# Gamebuino.net
KiCad netlist of a schematic drawn in Altium Designer
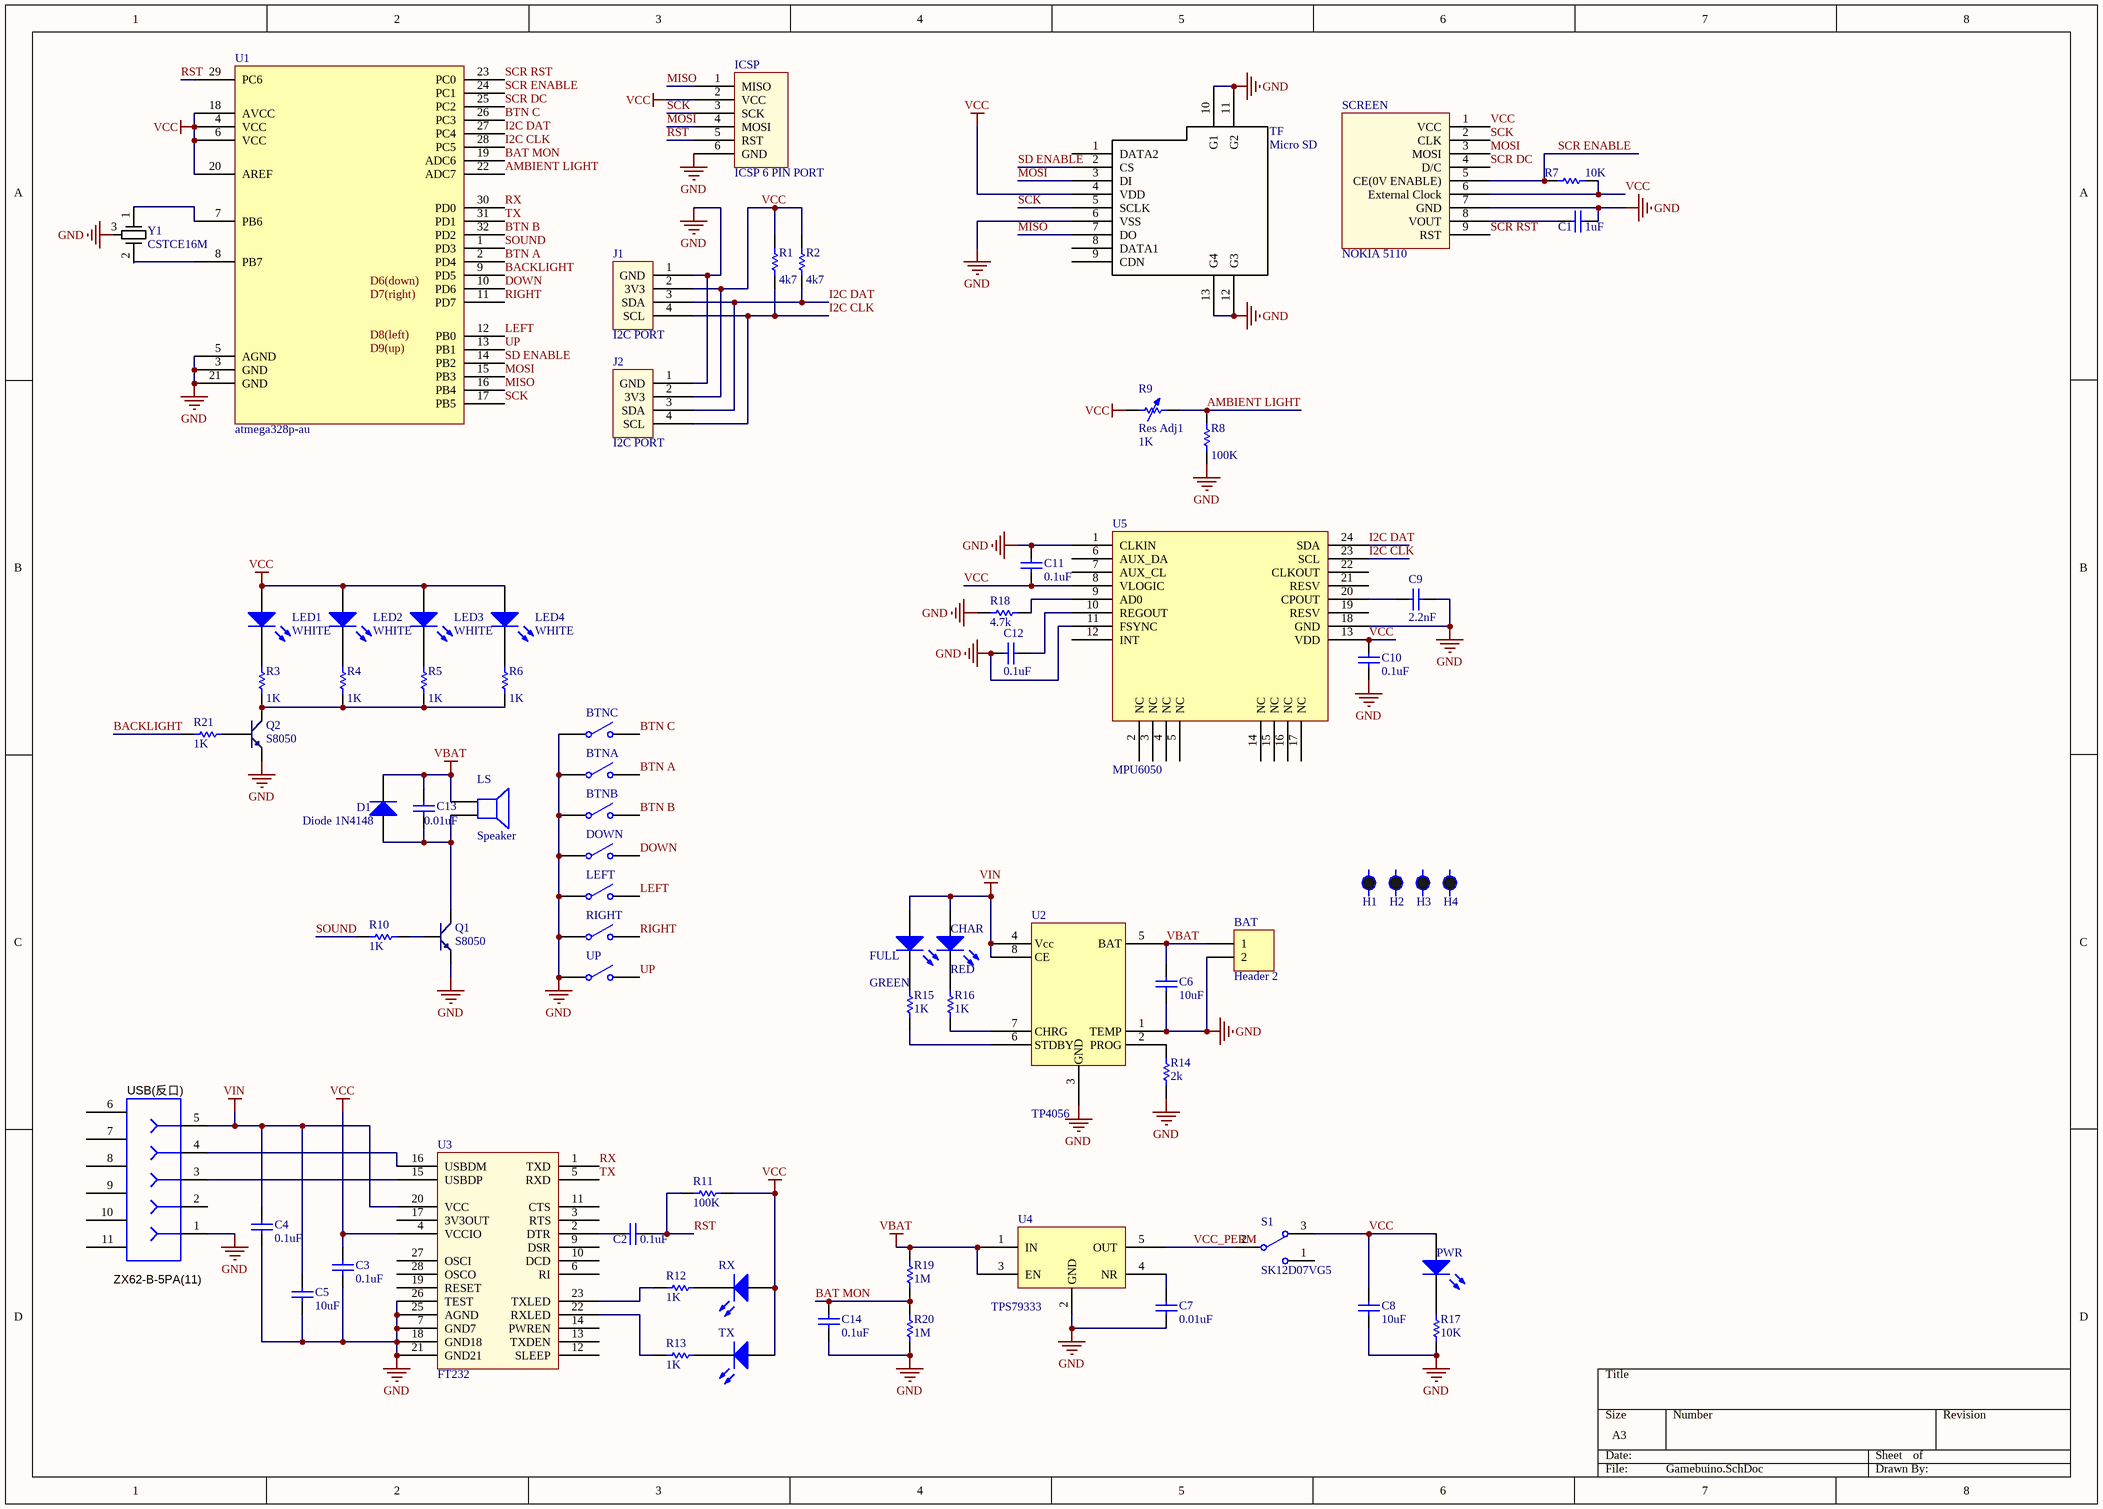
[diagram p0: Gamebuino.SchDoc]

(export (version "E")
  (design (tool "Eeschema 10.0.6"))
  (components
    (comp (ref "BAT")
      (value "Header 2")
      (footprint "BAT")
      (description "Header, 2-Pin")
      (fields (field (name "PUBLISHER") "Altium Limited"))
      (libsource (lib "Miscellaneous Connectors") (part "Header 2"))
    )
    (comp (ref "BTNA")
      (value "SW-SPST")
      (footprint "KEY5")
      (description "Single-Pole, Single-Throw Switch")
      (fields (field (name "PUBLISHER") "Altium Limited"))
      (libsource (lib "Miscellaneous Devices") (part "SW-SPST"))
    )
    (comp (ref "BTNB")
      (value "SW-SPST")
      (footprint "KEY5")
      (description "Single-Pole, Single-Throw Switch")
      (fields (field (name "PUBLISHER") "Altium Limited"))
      (libsource (lib "Miscellaneous Devices") (part "SW-SPST"))
    )
    (comp (ref "BTNC")
      (value "SW-SPST")
      (footprint "KEY5")
      (description "Single-Pole, Single-Throw Switch")
      (fields (field (name "PUBLISHER") "Altium Limited"))
      (libsource (lib "Miscellaneous Devices") (part "SW-SPST"))
    )
    (comp (ref "C1")
      (value "1uF")
      (footprint "6-0805_N")
      (description "Capacitor")
      (fields (field (name "Comment") "Cap") (field (name "PUBLISHER") "Altium Limited"))
      (libsource (lib "Miscellaneous Devices") (part "Cap"))
    )
    (comp (ref "C2")
      (value "0.1uF")
      (footprint "6-0805_N")
      (description "Capacitor")
      (fields (field (name "Comment") "Cap") (field (name "PUBLISHER") "Altium Limited"))
      (libsource (lib "Miscellaneous Devices") (part "Cap"))
    )
    (comp (ref "C3")
      (value "0.1uF")
      (footprint "6-0805_N")
      (description "Capacitor")
      (fields (field (name "Comment") "Cap") (field (name "PUBLISHER") "Altium Limited"))
      (libsource (lib "Miscellaneous Devices") (part "Cap"))
    )
    (comp (ref "C4")
      (value "0.1uF")
      (footprint "6-0805_N")
      (description "Capacitor")
      (fields (field (name "Comment") "Cap") (field (name "PUBLISHER") "Altium Limited"))
      (libsource (lib "Miscellaneous Devices") (part "Cap"))
    )
    (comp (ref "C5")
      (value "10uF")
      (footprint "6-0805_N")
      (description "Capacitor")
      (fields (field (name "Comment") "Cap") (field (name "PUBLISHER") "Altium Limited"))
      (libsource (lib "Miscellaneous Devices") (part "Cap"))
    )
    (comp (ref "C6")
      (value "10uF")
      (footprint "6-0805_N")
      (description "Capacitor")
      (fields (field (name "Comment") "Cap") (field (name "PUBLISHER") "Altium Limited"))
      (libsource (lib "Miscellaneous Devices") (part "Cap"))
    )
    (comp (ref "C7")
      (value "0.01uF")
      (footprint "6-0805_N")
      (description "Capacitor")
      (fields (field (name "Comment") "Cap") (field (name "PUBLISHER") "Altium Limited"))
      (libsource (lib "Miscellaneous Devices") (part "Cap"))
    )
    (comp (ref "C8")
      (value "10uF")
      (footprint "6-0805_N")
      (description "Capacitor")
      (fields (field (name "Comment") "Cap") (field (name "PUBLISHER") "Altium Limited"))
      (libsource (lib "Miscellaneous Devices") (part "Cap"))
    )
    (comp (ref "C9")
      (value "2.2nF")
      (footprint "6-0805_N")
      (description "Capacitor")
      (fields (field (name "Comment") "Cap") (field (name "PUBLISHER") "Altium Limited"))
      (libsource (lib "Miscellaneous Devices") (part "Cap"))
    )
    (comp (ref "C10")
      (value "0.1uF")
      (footprint "6-0805_N")
      (description "Capacitor")
      (fields (field (name "Comment") "Cap") (field (name "PUBLISHER") "Altium Limited"))
      (libsource (lib "Miscellaneous Devices") (part "Cap"))
    )
    (comp (ref "C11")
      (value "0.1uF")
      (footprint "6-0805_N")
      (description "Capacitor")
      (fields (field (name "Comment") "Cap") (field (name "PUBLISHER") "Altium Limited"))
      (libsource (lib "Miscellaneous Devices") (part "Cap"))
    )
    (comp (ref "C12")
      (value "0.1uF")
      (footprint "6-0805_N")
      (description "Capacitor")
      (fields (field (name "Comment") "Cap") (field (name "PUBLISHER") "Altium Limited"))
      (libsource (lib "Miscellaneous Devices") (part "Cap"))
    )
    (comp (ref "C13")
      (value "0.01uF")
      (footprint "6-0805_N")
      (description "Capacitor")
      (fields (field (name "Comment") "Cap") (field (name "PUBLISHER") "Altium Limited"))
      (libsource (lib "Miscellaneous Devices") (part "Cap"))
    )
    (comp (ref "C14")
      (value "0.1uF")
      (footprint "6-0805_N")
      (description "Capacitor")
      (fields (field (name "Comment") "Cap") (field (name "PUBLISHER") "Altium Limited"))
      (libsource (lib "Miscellaneous Devices") (part "Cap"))
    )
    (comp (ref "CHAR")
      (value "RED")
      (footprint "6-0805_N")
      (description "Typical INFRARED GaAs LED")
      (fields (field (name "PUBLISHER") "Altium Limited"))
      (libsource (lib "Miscellaneous Devices") (part "LED0"))
    )
    (comp (ref "D1")
      (value "Diode 1N4148")
      (footprint "12Z-2010")
      (description "High Conductance Fast Diode")
      (fields (field (name "PUBLISHER") "Altium Limited"))
      (libsource (lib "Miscellaneous Devices") (part "Diode 1N4148"))
    )
    (comp (ref "DOWN")
      (value "SW-SPST")
      (footprint "KEY5")
      (description "Single-Pole, Single-Throw Switch")
      (fields (field (name "PUBLISHER") "Altium Limited"))
      (libsource (lib "Miscellaneous Devices") (part "SW-SPST"))
    )
    (comp (ref "FULL")
      (value "GREEN")
      (footprint "6-0805_N")
      (description "Typical INFRARED GaAs LED")
      (fields (field (name "PUBLISHER") "Altium Limited"))
      (libsource (lib "Miscellaneous Devices") (part "LED0"))
    )
    (comp (ref "H1") (value "HOLE") (footprint "HOLE_3.0") (libsource (lib "mp3_digital") (part "HOLE")))
    (comp (ref "H2") (value "HOLE") (footprint "HOLE_3.0") (libsource (lib "mp3_digital") (part "HOLE")))
    (comp (ref "H3") (value "HOLE") (footprint "HOLE_3.0") (libsource (lib "mp3_digital") (part "HOLE")))
    (comp (ref "H4") (value "HOLE") (footprint "HOLE_3.0") (libsource (lib "mp3_digital") (part "HOLE")))
    (comp (ref "ICSP")
      (value "ICSP 6 PIN PORT")
      (footprint "CONN6-1mm")
      (libsource (lib "Gamebuino") (part "ICSP"))
    )
    (comp (ref "J1")
      (value "I2C PORT")
      (footprint "CONN4_/wTestPoint")
      (libsource (lib "Gamebuino") (part "Component_1"))
    )
    (comp (ref "J2")
      (value "I2C PORT")
      (footprint "CONN4_/wTestPoint")
      (libsource (lib "Gamebuino") (part "Component_1"))
    )
    (comp (ref "LED1")
      (value "WHITE")
      (footprint "6-0805_N")
      (description "Typical INFRARED GaAs LED")
      (fields (field (name "PUBLISHER") "Altium Limited"))
      (libsource (lib "Miscellaneous Devices") (part "LED0"))
    )
    (comp (ref "LED2")
      (value "WHITE")
      (footprint "6-0805_N")
      (description "Typical INFRARED GaAs LED")
      (fields (field (name "PUBLISHER") "Altium Limited"))
      (libsource (lib "Miscellaneous Devices") (part "LED0"))
    )
    (comp (ref "LED3")
      (value "WHITE")
      (footprint "6-0805_N")
      (description "Typical INFRARED GaAs LED")
      (fields (field (name "PUBLISHER") "Altium Limited"))
      (libsource (lib "Miscellaneous Devices") (part "LED0"))
    )
    (comp (ref "LED4")
      (value "WHITE")
      (footprint "6-0805_N")
      (description "Typical INFRARED GaAs LED")
      (fields (field (name "PUBLISHER") "Altium Limited"))
      (libsource (lib "Miscellaneous Devices") (part "LED0"))
    )
    (comp (ref "LEFT")
      (value "SW-SPST")
      (footprint "KEY5")
      (description "Single-Pole, Single-Throw Switch")
      (fields (field (name "PUBLISHER") "Altium Limited"))
      (libsource (lib "Miscellaneous Devices") (part "SW-SPST"))
    )
    (comp (ref "LS")
      (value "Speaker")
      (footprint "Speaker")
      (description "Loudspeaker")
      (fields (field (name "PUBLISHER") "Altium Limited"))
      (libsource (lib "Miscellaneous Devices") (part "Speaker"))
    )
    (comp (ref "PWR")
      (value "LED0")
      (footprint "6-0805_N")
      (description "Typical INFRARED GaAs LED")
      (fields (field (name "PUBLISHER") "Altium Limited"))
      (libsource (lib "Miscellaneous Devices") (part "LED0"))
    )
    (comp (ref "Q1")
      (value "S8050")
      (footprint "SOT-23R")
      (description "8050/BCW846/BCW847")
      (libsource (lib "mp3_analog") (part "NPN"))
    )
    (comp (ref "Q2")
      (value "S8050")
      (footprint "SOT-23R")
      (description "8050/BCW846/BCW847")
      (libsource (lib "mp3_analog") (part "NPN"))
    )
    (comp (ref "R1")
      (value "4k7")
      (footprint "6-0805_N")
      (description "Resistor")
      (fields (field (name "Comment") "Res1") (field (name "PUBLISHER") "Altium Limited"))
      (libsource (lib "Miscellaneous Devices") (part "Res1"))
    )
    (comp (ref "R2")
      (value "4k7")
      (footprint "6-0805_N")
      (description "Resistor")
      (fields (field (name "Comment") "Res1") (field (name "PUBLISHER") "Altium Limited"))
      (libsource (lib "Miscellaneous Devices") (part "Res1"))
    )
    (comp (ref "R3")
      (value "1K")
      (footprint "6-0805_N")
      (description "Resistor")
      (fields (field (name "Comment") "Res1") (field (name "PUBLISHER") "Altium Limited"))
      (libsource (lib "Miscellaneous Devices") (part "Res1"))
    )
    (comp (ref "R4")
      (value "1K")
      (footprint "6-0805_N")
      (description "Resistor")
      (fields (field (name "Comment") "Res1") (field (name "PUBLISHER") "Altium Limited"))
      (libsource (lib "Miscellaneous Devices") (part "Res1"))
    )
    (comp (ref "R5")
      (value "1K")
      (footprint "6-0805_N")
      (description "Resistor")
      (fields (field (name "Comment") "Res1") (field (name "PUBLISHER") "Altium Limited"))
      (libsource (lib "Miscellaneous Devices") (part "Res1"))
    )
    (comp (ref "R6")
      (value "1K")
      (footprint "6-0805_N")
      (description "Resistor")
      (fields (field (name "Comment") "Res1") (field (name "PUBLISHER") "Altium Limited"))
      (libsource (lib "Miscellaneous Devices") (part "Res1"))
    )
    (comp (ref "R7")
      (value "10K")
      (footprint "6-0805_N")
      (description "Resistor")
      (fields (field (name "Comment") "Res1") (field (name "PUBLISHER") "Altium Limited"))
      (libsource (lib "Miscellaneous Devices") (part "Res1"))
    )
    (comp (ref "R8")
      (value "100K")
      (footprint "6-0805_N")
      (description "Resistor")
      (fields (field (name "Comment") "Res1") (field (name "PUBLISHER") "Altium Limited"))
      (libsource (lib "Miscellaneous Devices") (part "Res1"))
    )
    (comp (ref "R9")
      (value "Res Adj1")
      (footprint "light_sensor")
      (description "Variable Resistor")
      (fields (field (name "ALTIUM_VALUE") "1K") (field (name "PUBLISHER") "Altium Limited"))
      (libsource (lib "Miscellaneous Devices") (part "Res Adj1"))
    )
    (comp (ref "R10")
      (value "1K")
      (footprint "6-0805_N")
      (description "Resistor")
      (fields (field (name "Comment") "Res1") (field (name "PUBLISHER") "Altium Limited"))
      (libsource (lib "Miscellaneous Devices") (part "Res1"))
    )
    (comp (ref "R11")
      (value "100K")
      (footprint "6-0805_N")
      (description "Resistor")
      (fields (field (name "Comment") "Res1") (field (name "PUBLISHER") "Altium Limited"))
      (libsource (lib "Miscellaneous Devices") (part "Res1"))
    )
    (comp (ref "R12")
      (value "1K")
      (footprint "6-0805_N")
      (description "Resistor")
      (fields (field (name "Comment") "Res1") (field (name "PUBLISHER") "Altium Limited"))
      (libsource (lib "Miscellaneous Devices") (part "Res1"))
    )
    (comp (ref "R13")
      (value "1K")
      (footprint "6-0805_N")
      (description "Resistor")
      (fields (field (name "Comment") "Res1") (field (name "PUBLISHER") "Altium Limited"))
      (libsource (lib "Miscellaneous Devices") (part "Res1"))
    )
    (comp (ref "R14")
      (value "2k")
      (footprint "6-0805_N")
      (description "Resistor")
      (fields (field (name "Comment") "Res1") (field (name "PUBLISHER") "Altium Limited"))
      (libsource (lib "Miscellaneous Devices") (part "Res1"))
    )
    (comp (ref "R15")
      (value "1K")
      (footprint "6-0805_N")
      (description "Resistor")
      (fields (field (name "Comment") "Res1") (field (name "PUBLISHER") "Altium Limited"))
      (libsource (lib "Miscellaneous Devices") (part "Res1"))
    )
    (comp (ref "R16")
      (value "1K")
      (footprint "6-0805_N")
      (description "Resistor")
      (fields (field (name "Comment") "Res1") (field (name "PUBLISHER") "Altium Limited"))
      (libsource (lib "Miscellaneous Devices") (part "Res1"))
    )
    (comp (ref "R17")
      (value "10K")
      (footprint "6-0805_N")
      (description "Resistor")
      (fields (field (name "Comment") "Res1") (field (name "PUBLISHER") "Altium Limited"))
      (libsource (lib "Miscellaneous Devices") (part "Res1"))
    )
    (comp (ref "R18")
      (value "4.7k")
      (footprint "6-0805_N")
      (description "Resistor")
      (fields (field (name "Comment") "Res1") (field (name "PUBLISHER") "Altium Limited"))
      (libsource (lib "Miscellaneous Devices") (part "Res1"))
    )
    (comp (ref "R19")
      (value "1M")
      (footprint "6-0805_N")
      (description "Resistor")
      (fields (field (name "Comment") "Res1") (field (name "PUBLISHER") "Altium Limited"))
      (libsource (lib "Miscellaneous Devices") (part "Res1"))
    )
    (comp (ref "R20")
      (value "1M")
      (footprint "6-0805_N")
      (description "Resistor")
      (fields (field (name "Comment") "Res1") (field (name "PUBLISHER") "Altium Limited"))
      (libsource (lib "Miscellaneous Devices") (part "Res1"))
    )
    (comp (ref "R21")
      (value "1K")
      (footprint "6-0805_N")
      (description "Resistor")
      (fields (field (name "Comment") "Res1") (field (name "PUBLISHER") "Altium Limited"))
      (libsource (lib "Miscellaneous Devices") (part "Res1"))
    )
    (comp (ref "RIGHT")
      (value "SW-SPST")
      (footprint "KEY5")
      (description "Single-Pole, Single-Throw Switch")
      (fields (field (name "PUBLISHER") "Altium Limited"))
      (libsource (lib "Miscellaneous Devices") (part "SW-SPST"))
    )
    (comp (ref "RX")
      (value "LED0")
      (footprint "6-0805_N")
      (description "Typical INFRARED GaAs LED")
      (fields (field (name "PUBLISHER") "Altium Limited"))
      (libsource (lib "Miscellaneous Devices") (part "LED0"))
    )
    (comp (ref "S1")
      (value "SK12D07VG5")
      (footprint "DIP10")
      (description "SPDT Subminiature Toggle Switch, Right Angle Mounting, Vertical Actuation")
      (fields (field (name "PUBLISHER") "Altium Limited"))
      (libsource (lib "Miscellaneous Devices") (part "SW-SPDT"))
    )
    (comp (ref "SCREEN")
      (value "NOKIA 5110")
      (footprint "5110_bare")
      (libsource (lib "Gamebuino") (part "NOKIA 5110"))
    )
    (comp (ref "TF") (value "Micro SD") (footprint "tf") (libsource (lib "MP3 NANO") (part "Micro SD")))
    (comp (ref "TX")
      (value "LED0")
      (footprint "6-0805_N")
      (description "Typical INFRARED GaAs LED")
      (fields (field (name "PUBLISHER") "Altium Limited"))
      (libsource (lib "Miscellaneous Devices") (part "LED0"))
    )
    (comp (ref "U1")
      (value "atmega328p-au")
      (footprint "TQFP-32N-1")
      (libsource (lib "dakaqi") (part "atmega328p-au"))
    )
    (comp (ref "U2") (value "TP4056") (footprint "SOP-PP-8") (libsource (lib "mp3_digital") (part "TP4056")))
    (comp (ref "U3")
      (value "FT232")
      (footprint "LC-SSOP-28_208mil")
      (libsource (lib "Gamebuino") (part "FT232"))
    )
    (comp (ref "U4")
      (value "TPS79333")
      (footprint "SOT-23-5")
      (libsource (lib "mp3_analog") (part "TPS79333"))
    )
    (comp (ref "U5") (value "MPU6050") (footprint "QFN-24A") (libsource (lib "microsizhou") (part "MPU6050")))
    (comp (ref "UP")
      (value "SW-SPST")
      (footprint "KEY5")
      (description "Single-Pole, Single-Throw Switch")
      (fields (field (name "PUBLISHER") "Altium Limited"))
      (libsource (lib "Miscellaneous Devices") (part "SW-SPST"))
    )
    (comp (ref "USB(反口)")
      (value "ZX62-B-5PA(11)")
      (footprint "CONN_USB_micro_ZX62-B-5PA")
      (description "Connector, micro USB Type B, Receptacle, R/A, SMD")
      (fields
        (field (name "MANUFACTURER") "Hirose Electric Co. Ltd.")
        (field (name "SYMBOLCREATOR") "a0411947")
        (field (name "PUBLISHER") "Texas Instruments")
      )
      (libsource (lib "Focus1Beta1STM32") (part "ZX62M-B-5P"))
    )
    (comp (ref "Y1") (value "CSTCE16M") (footprint "cstce8m") (libsource (lib "dakaqi") (part "cstce8m")))
  )
  (nets
    (net (code "1") (name "/AMBIENT LIGHT") (class "Default")
      (node (ref "R8") (pin "2") (pinfunction "2_2") (pintype "passive"))
      (node (ref "R9") (pin "2") (pinfunction "2_2") (pintype "passive"))
      (node (ref "U1") (pin "22") (pinfunction "ADC7_22") (pintype "passive"))
    )
    (net (code "2") (name "/BACKLIGHT") (class "Default")
      (node (ref "R21") (pin "1") (pinfunction "1_1") (pintype "passive"))
      (node (ref "U1") (pin "9") (pinfunction "PD5_9") (pintype "passive"))
    )
    (net (code "3") (name "/BAT MON") (class "Default")
      (node (ref "C14") (pin "1") (pinfunction "1_1") (pintype "passive"))
      (node (ref "R19") (pin "1") (pinfunction "1_1") (pintype "passive"))
      (node (ref "R20") (pin "2") (pinfunction "2_2") (pintype "passive"))
      (node (ref "U1") (pin "19") (pinfunction "ADC6_19") (pintype "passive"))
    )
    (net (code "4") (name "/BTN A") (class "Default")
      (node (ref "BTNA") (pin "2") (pinfunction "NO_2") (pintype "passive"))
      (node (ref "U1") (pin "2") (pinfunction "PD4_2") (pintype "passive"))
    )
    (net (code "5") (name "/BTN B") (class "Default")
      (node (ref "BTNB") (pin "2") (pinfunction "NO_2") (pintype "passive"))
      (node (ref "U1") (pin "32") (pinfunction "PD2_32") (pintype "passive"))
    )
    (net (code "6") (name "/BTN C") (class "Default")
      (node (ref "BTNC") (pin "2") (pinfunction "NO_2") (pintype "passive"))
      (node (ref "U1") (pin "26") (pinfunction "PC3_26") (pintype "passive"))
    )
    (net (code "11") (name "/DOWN") (class "Default")
      (node (ref "DOWN") (pin "2") (pinfunction "NO_2") (pintype "passive"))
      (node (ref "U1") (pin "10") (pinfunction "PD6_10") (pintype "passive"))
    )
    (net (code "12") (name "/I2C CLK") (class "Default")
      (node (ref "J1") (pin "4") (pinfunction "SCL_4") (pintype "passive"))
      (node (ref "J2") (pin "4") (pinfunction "SCL_4") (pintype "passive"))
      (node (ref "R1") (pin "1") (pinfunction "1_1") (pintype "passive"))
      (node (ref "U1") (pin "28") (pinfunction "PC5_28") (pintype "passive"))
      (node (ref "U5") (pin "23") (pinfunction "SCL_23") (pintype "passive"))
    )
    (net (code "13") (name "/I2C DAT") (class "Default")
      (node (ref "J1") (pin "3") (pinfunction "SDA_3") (pintype "passive"))
      (node (ref "J2") (pin "3") (pinfunction "SDA_3") (pintype "passive"))
      (node (ref "R2") (pin "1") (pinfunction "1_1") (pintype "passive"))
      (node (ref "U1") (pin "27") (pinfunction "PC4_27") (pintype "passive"))
      (node (ref "U5") (pin "24") (pinfunction "SDA_24") (pintype "passive"))
    )
    (net (code "14") (name "/LEFT") (class "Default")
      (node (ref "LEFT") (pin "2") (pinfunction "NO_2") (pintype "passive"))
      (node (ref "U1") (pin "12") (pinfunction "PB0_12") (pintype "passive"))
    )
    (net (code "15") (name "/MISO") (class "Default")
      (node (ref "ICSP") (pin "1") (pinfunction "MISO_1") (pintype "passive"))
      (node (ref "TF") (pin "7") (pinfunction "DO_7") (pintype "passive"))
      (node (ref "U1") (pin "16") (pinfunction "PB4_16") (pintype "passive"))
    )
    (net (code "16") (name "/MOSI") (class "Default")
      (node (ref "ICSP") (pin "4") (pinfunction "MOSI_4") (pintype "passive"))
      (node (ref "SCREEN") (pin "3") (pinfunction "MOSI_3") (pintype "passive"))
      (node (ref "TF") (pin "3") (pinfunction "DI_3") (pintype "passive"))
      (node (ref "U1") (pin "15") (pinfunction "PB3_15") (pintype "passive"))
    )
    (net (code "17") (name "/RIGHT") (class "Default")
      (node (ref "RIGHT") (pin "2") (pinfunction "NO_2") (pintype "passive"))
      (node (ref "U1") (pin "11") (pinfunction "PD7_11") (pintype "passive"))
    )
    (net (code "18") (name "/RST") (class "Default")
      (node (ref "C2") (pin "2") (pinfunction "2_2") (pintype "passive"))
      (node (ref "ICSP") (pin "5") (pinfunction "RST_5") (pintype "passive"))
      (node (ref "R11") (pin "2") (pinfunction "2_2") (pintype "passive"))
      (node (ref "U1") (pin "29") (pinfunction "PC6_29") (pintype "passive"))
    )
    (net (code "19") (name "/RX") (class "Default")
      (node (ref "U1") (pin "30") (pinfunction "PD0_30") (pintype "passive"))
      (node (ref "U3") (pin "1") (pinfunction "TXD_1") (pintype "passive"))
    )
    (net (code "20") (name "/SCK") (class "Default")
      (node (ref "ICSP") (pin "3") (pinfunction "SCK_3") (pintype "passive"))
      (node (ref "SCREEN") (pin "2") (pinfunction "CLK_2") (pintype "passive"))
      (node (ref "TF") (pin "5") (pinfunction "SCLK_5") (pintype "passive"))
      (node (ref "U1") (pin "17") (pinfunction "PB5_17") (pintype "passive"))
    )
    (net (code "21") (name "/SCR DC") (class "Default")
      (node (ref "SCREEN") (pin "4") (pinfunction "D/C_4") (pintype "passive"))
      (node (ref "U1") (pin "25") (pinfunction "PC2_25") (pintype "passive"))
    )
    (net (code "22") (name "/SCR ENABLE") (class "Default")
      (node (ref "R7") (pin "2") (pinfunction "2_2") (pintype "passive"))
      (node (ref "SCREEN") (pin "5") (pinfunction "CE(0V_ENABLE)_5") (pintype "passive"))
      (node (ref "U1") (pin "24") (pinfunction "PC1_24") (pintype "passive"))
    )
    (net (code "23") (name "/SCR RST") (class "Default")
      (node (ref "SCREEN") (pin "9") (pinfunction "RST_9") (pintype "passive"))
      (node (ref "U1") (pin "23") (pinfunction "PC0_23") (pintype "passive"))
    )
    (net (code "24") (name "/SD ENABLE") (class "Default")
      (node (ref "TF") (pin "2") (pinfunction "CS_2") (pintype "passive"))
      (node (ref "U1") (pin "14") (pinfunction "PB2_14") (pintype "passive"))
    )
    (net (code "25") (name "/SOUND") (class "Default")
      (node (ref "R10") (pin "2") (pinfunction "2_2") (pintype "passive"))
      (node (ref "U1") (pin "1") (pinfunction "PD3_1") (pintype "passive"))
    )
    (net (code "26") (name "/TX") (class "Default")
      (node (ref "U1") (pin "31") (pinfunction "PD1_31") (pintype "passive"))
      (node (ref "U3") (pin "5") (pinfunction "RXD_5") (pintype "passive"))
    )
    (net (code "27") (name "/UP") (class "Default")
      (node (ref "U1") (pin "13") (pinfunction "PB1_13") (pintype "passive"))
      (node (ref "UP") (pin "2") (pinfunction "NO_2") (pintype "passive"))
    )
    (net (code "28") (name "/VCC_PERM") (class "Default")
      (node (ref "S1") (pin "2") (pinfunction "2_2") (pintype "passive"))
      (node (ref "U4") (pin "5") (pinfunction "OUT_5") (pintype "passive"))
    )
    (net (code "29") (name "GND") (class "Default")
      (node (ref "BAT") (pin "2") (pinfunction "2_2") (pintype "passive"))
      (node (ref "BTNA") (pin "1") (pinfunction "COMMON_1") (pintype "passive"))
      (node (ref "BTNB") (pin "1") (pinfunction "COMMON_1") (pintype "passive"))
      (node (ref "BTNC") (pin "1") (pinfunction "COMMON_1") (pintype "passive"))
      (node (ref "C1") (pin "2") (pinfunction "2_2") (pintype "passive"))
      (node (ref "C10") (pin "1") (pinfunction "1_1") (pintype "passive"))
      (node (ref "C11") (pin "2") (pinfunction "2_2") (pintype "passive"))
      (node (ref "C12") (pin "2") (pinfunction "2_2") (pintype "passive"))
      (node (ref "C14") (pin "2") (pinfunction "2_2") (pintype "passive"))
      (node (ref "C3") (pin "1") (pinfunction "1_1") (pintype "passive"))
      (node (ref "C4") (pin "1") (pinfunction "1_1") (pintype "passive"))
      (node (ref "C5") (pin "1") (pinfunction "1_1") (pintype "passive"))
      (node (ref "C6") (pin "1") (pinfunction "1_1") (pintype "passive"))
      (node (ref "C7") (pin "1") (pinfunction "1_1") (pintype "passive"))
      (node (ref "C8") (pin "1") (pinfunction "1_1") (pintype "passive"))
      (node (ref "C9") (pin "1") (pinfunction "1_1") (pintype "passive"))
      (node (ref "DOWN") (pin "1") (pinfunction "COMMON_1") (pintype "passive"))
      (node (ref "ICSP") (pin "6") (pinfunction "GND_6") (pintype "passive"))
      (node (ref "J1") (pin "1") (pinfunction "GND_1") (pintype "passive"))
      (node (ref "J2") (pin "1") (pinfunction "GND_1") (pintype "passive"))
      (node (ref "LEFT") (pin "1") (pinfunction "COMMON_1") (pintype "passive"))
      (node (ref "Q1") (pin "1") (pinfunction "E_1") (pintype "passive"))
      (node (ref "Q2") (pin "1") (pinfunction "E_1") (pintype "passive"))
      (node (ref "R14") (pin "2") (pinfunction "2_2") (pintype "passive"))
      (node (ref "R17") (pin "2") (pinfunction "2_2") (pintype "passive"))
      (node (ref "R18") (pin "1") (pinfunction "1_1") (pintype "passive"))
      (node (ref "R20") (pin "1") (pinfunction "1_1") (pintype "passive"))
      (node (ref "R8") (pin "1") (pinfunction "1_1") (pintype "passive"))
      (node (ref "RIGHT") (pin "1") (pinfunction "COMMON_1") (pintype "passive"))
      (node (ref "SCREEN") (pin "7") (pinfunction "GND_7") (pintype "passive"))
      (node (ref "TF") (pin "10") (pinfunction "G1_10") (pintype "passive"))
      (node (ref "TF") (pin "11") (pinfunction "G2_11") (pintype "passive"))
      (node (ref "TF") (pin "12") (pinfunction "G3_12") (pintype "passive"))
      (node (ref "TF") (pin "13") (pinfunction "G4_13") (pintype "passive"))
      (node (ref "TF") (pin "6") (pinfunction "VSS_6") (pintype "passive"))
      (node (ref "U1") (pin "21") (pinfunction "GND_21") (pintype "passive"))
      (node (ref "U1") (pin "3") (pinfunction "GND_3") (pintype "passive"))
      (node (ref "U1") (pin "5") (pinfunction "AGND_5") (pintype "passive"))
      (node (ref "U2") (pin "1") (pinfunction "TEMP_1") (pintype "passive"))
      (node (ref "U2") (pin "3") (pinfunction "GND_3") (pintype "passive"))
      (node (ref "U3") (pin "18") (pinfunction "GND18_18") (pintype "passive"))
      (node (ref "U3") (pin "21") (pinfunction "GND21_21") (pintype "passive"))
      (node (ref "U3") (pin "25") (pinfunction "AGND_25") (pintype "passive"))
      (node (ref "U3") (pin "26") (pinfunction "TEST_26") (pintype "passive"))
      (node (ref "U3") (pin "7") (pinfunction "GND7_7") (pintype "passive"))
      (node (ref "U4") (pin "2") (pinfunction "GND_2") (pintype "passive"))
      (node (ref "U5") (pin "1") (pinfunction "CLKIN_1") (pintype "passive"))
      (node (ref "U5") (pin "11") (pinfunction "FSYNC_11") (pintype "passive"))
      (node (ref "U5") (pin "18") (pinfunction "GND_18") (pintype "passive"))
      (node (ref "UP") (pin "1") (pinfunction "COMMON_1") (pintype "passive"))
      (node (ref "USB(反口)") (pin "1") (pinfunction "1_1") (pintype "passive"))
      (node (ref "Y1") (pin "3") (pinfunction "3_3") (pintype "passive"))
    )
    (net (code "30") (name "Net-(CHAR-K)") (class "Default")
      (node (ref "CHAR") (pin "2") (pinfunction "K_2") (pintype "passive"))
      (node (ref "R16") (pin "1") (pinfunction "1_1") (pintype "passive"))
    )
    (net (code "31") (name "Net-(D1-A)") (class "Default")
      (node (ref "C13") (pin "2") (pinfunction "2_2") (pintype "passive"))
      (node (ref "D1") (pin "1") (pinfunction "A_1") (pintype "passive"))
      (node (ref "LS") (pin "2") (pinfunction "2_2") (pintype "passive"))
      (node (ref "Q1") (pin "3") (pinfunction "C_3") (pintype "passive"))
    )
    (net (code "32") (name "Net-(FULL-K)") (class "Default")
      (node (ref "FULL") (pin "2") (pinfunction "K_2") (pintype "passive"))
      (node (ref "R15") (pin "1") (pinfunction "1_1") (pintype "passive"))
    )
    (net (code "33") (name "Net-(LED1-K)") (class "Default")
      (node (ref "LED1") (pin "2") (pinfunction "K_2") (pintype "passive"))
      (node (ref "R3") (pin "2") (pinfunction "2_2") (pintype "passive"))
    )
    (net (code "34") (name "Net-(LED2-K)") (class "Default")
      (node (ref "LED2") (pin "2") (pinfunction "K_2") (pintype "passive"))
      (node (ref "R4") (pin "2") (pinfunction "2_2") (pintype "passive"))
    )
    (net (code "35") (name "Net-(LED3-K)") (class "Default")
      (node (ref "LED3") (pin "2") (pinfunction "K_2") (pintype "passive"))
      (node (ref "R5") (pin "2") (pinfunction "2_2") (pintype "passive"))
    )
    (net (code "36") (name "Net-(LED4-K)") (class "Default")
      (node (ref "LED4") (pin "2") (pinfunction "K_2") (pintype "passive"))
      (node (ref "R6") (pin "2") (pinfunction "2_2") (pintype "passive"))
    )
    (net (code "37") (name "Net-(PWR-K)") (class "Default")
      (node (ref "PWR") (pin "2") (pinfunction "K_2") (pintype "passive"))
      (node (ref "R17") (pin "1") (pinfunction "1_1") (pintype "passive"))
    )
    (net (code "38") (name "Net-(Q1-B)") (class "Default")
      (node (ref "Q1") (pin "2") (pinfunction "B_2") (pintype "passive"))
      (node (ref "R10") (pin "1") (pinfunction "1_1") (pintype "passive"))
    )
    (net (code "39") (name "Net-(Q2-B)") (class "Default")
      (node (ref "Q2") (pin "2") (pinfunction "B_2") (pintype "passive"))
      (node (ref "R21") (pin "2") (pinfunction "2_2") (pintype "passive"))
    )
    (net (code "40") (name "Net-(Q2-C)") (class "Default")
      (node (ref "Q2") (pin "3") (pinfunction "C_3") (pintype "passive"))
      (node (ref "R3") (pin "1") (pinfunction "1_1") (pintype "passive"))
      (node (ref "R4") (pin "1") (pinfunction "1_1") (pintype "passive"))
      (node (ref "R5") (pin "1") (pinfunction "1_1") (pintype "passive"))
      (node (ref "R6") (pin "1") (pinfunction "1_1") (pintype "passive"))
    )
    (net (code "41") (name "Net-(RX-K)") (class "Default")
      (node (ref "R12") (pin "1") (pinfunction "1_1") (pintype "passive"))
      (node (ref "RX") (pin "2") (pinfunction "K_2") (pintype "passive"))
    )
    (net (code "42") (name "Net-(SCREEN-VOUT)") (class "Default")
      (node (ref "C1") (pin "1") (pinfunction "1_1") (pintype "passive"))
      (node (ref "SCREEN") (pin "8") (pinfunction "VOUT_8") (pintype "passive"))
    )
    (net (code "43") (name "Net-(TX-K)") (class "Default")
      (node (ref "R13") (pin "1") (pinfunction "1_1") (pintype "passive"))
      (node (ref "TX") (pin "2") (pinfunction "K_2") (pintype "passive"))
    )
    (net (code "44") (name "Net-(U1-PB6)") (class "Default")
      (node (ref "U1") (pin "7") (pinfunction "PB6_7") (pintype "passive"))
      (node (ref "Y1") (pin "1") (pinfunction "1_1") (pintype "passive"))
    )
    (net (code "45") (name "Net-(U1-PB7)") (class "Default")
      (node (ref "U1") (pin "8") (pinfunction "PB7_8") (pintype "passive"))
      (node (ref "Y1") (pin "2") (pinfunction "2_2") (pintype "passive"))
    )
    (net (code "46") (name "Net-(U2-CHRG)") (class "Default")
      (node (ref "R16") (pin "2") (pinfunction "2_2") (pintype "passive"))
      (node (ref "U2") (pin "7") (pinfunction "CHRG_7") (pintype "passive"))
    )
    (net (code "47") (name "Net-(U2-PROG)") (class "Default")
      (node (ref "R14") (pin "1") (pinfunction "1_1") (pintype "passive"))
      (node (ref "U2") (pin "2") (pinfunction "PROG_2") (pintype "passive"))
    )
    (net (code "48") (name "Net-(U2-STDBY)") (class "Default")
      (node (ref "R15") (pin "2") (pinfunction "2_2") (pintype "passive"))
      (node (ref "U2") (pin "6") (pinfunction "STDBY_6") (pintype "passive"))
    )
    (net (code "49") (name "Net-(U3-DTR)") (class "Default")
      (node (ref "C2") (pin "1") (pinfunction "1_1") (pintype "passive"))
      (node (ref "U3") (pin "2") (pinfunction "DTR_2") (pintype "passive"))
    )
    (net (code "50") (name "Net-(U3-RXLED)") (class "Default")
      (node (ref "R13") (pin "2") (pinfunction "2_2") (pintype "passive"))
      (node (ref "U3") (pin "22") (pinfunction "RXLED_22") (pintype "passive"))
    )
    (net (code "51") (name "Net-(U3-TXLED)") (class "Default")
      (node (ref "R12") (pin "2") (pinfunction "2_2") (pintype "passive"))
      (node (ref "U3") (pin "23") (pinfunction "TXLED_23") (pintype "passive"))
    )
    (net (code "52") (name "Net-(U3-USBDM)") (class "Default")
      (node (ref "U3") (pin "16") (pinfunction "USBDM_16") (pintype "passive"))
      (node (ref "USB(反口)") (pin "4") (pinfunction "4_4") (pintype "passive"))
    )
    (net (code "53") (name "Net-(U3-USBDP)") (class "Default")
      (node (ref "U3") (pin "15") (pinfunction "USBDP_15") (pintype "passive"))
      (node (ref "USB(反口)") (pin "3") (pinfunction "3_3") (pintype "passive"))
    )
    (net (code "54") (name "Net-(U4-NR)") (class "Default")
      (node (ref "C7") (pin "2") (pinfunction "2_2") (pintype "passive"))
      (node (ref "U4") (pin "4") (pinfunction "NR_4") (pintype "passive"))
    )
    (net (code "55") (name "Net-(U5-AD0)") (class "Default")
      (node (ref "R18") (pin "2") (pinfunction "2_2") (pintype "passive"))
      (node (ref "U5") (pin "9") (pinfunction "AD0_9") (pintype "passive"))
    )
    (net (code "56") (name "Net-(U5-CPOUT)") (class "Default")
      (node (ref "C9") (pin "2") (pinfunction "2_2") (pintype "passive"))
      (node (ref "U5") (pin "20") (pinfunction "CPOUT_20") (pintype "passive"))
    )
    (net (code "57") (name "Net-(U5-REGOUT)") (class "Default")
      (node (ref "C12") (pin "1") (pinfunction "1_1") (pintype "passive"))
      (node (ref "U5") (pin "10") (pinfunction "REGOUT_10") (pintype "passive"))
    )
    (net (code "58") (name "VBAT") (class "Default")
      (node (ref "BAT") (pin "1") (pinfunction "1_1") (pintype "passive"))
      (node (ref "C13") (pin "1") (pinfunction "1_1") (pintype "passive"))
      (node (ref "C6") (pin "2") (pinfunction "2_2") (pintype "passive"))
      (node (ref "D1") (pin "2") (pinfunction "K_2") (pintype "passive"))
      (node (ref "LS") (pin "1") (pinfunction "1_1") (pintype "passive"))
      (node (ref "R19") (pin "2") (pinfunction "2_2") (pintype "passive"))
      (node (ref "U2") (pin "5") (pinfunction "BAT_5") (pintype "passive"))
      (node (ref "U4") (pin "1") (pinfunction "IN_1") (pintype "passive"))
      (node (ref "U4") (pin "3") (pinfunction "EN_3") (pintype "passive"))
    )
    (net (code "59") (name "VCC") (class "Default")
      (node (ref "C10") (pin "2") (pinfunction "2_2") (pintype "passive"))
      (node (ref "C11") (pin "1") (pinfunction "1_1") (pintype "passive"))
      (node (ref "C3") (pin "2") (pinfunction "2_2") (pintype "passive"))
      (node (ref "C8") (pin "2") (pinfunction "2_2") (pintype "passive"))
      (node (ref "ICSP") (pin "2") (pinfunction "VCC_2") (pintype "passive"))
      (node (ref "J1") (pin "2") (pinfunction "3V3_2") (pintype "passive"))
      (node (ref "J2") (pin "2") (pinfunction "3V3_2") (pintype "passive"))
      (node (ref "LED1") (pin "1") (pinfunction "A_1") (pintype "passive"))
      (node (ref "LED2") (pin "1") (pinfunction "A_1") (pintype "passive"))
      (node (ref "LED3") (pin "1") (pinfunction "A_1") (pintype "passive"))
      (node (ref "LED4") (pin "1") (pinfunction "A_1") (pintype "passive"))
      (node (ref "PWR") (pin "1") (pinfunction "A_1") (pintype "passive"))
      (node (ref "R1") (pin "2") (pinfunction "2_2") (pintype "passive"))
      (node (ref "R11") (pin "1") (pinfunction "1_1") (pintype "passive"))
      (node (ref "R2") (pin "2") (pinfunction "2_2") (pintype "passive"))
      (node (ref "R7") (pin "1") (pinfunction "1_1") (pintype "passive"))
      (node (ref "R9") (pin "1") (pinfunction "1_1") (pintype "passive"))
      (node (ref "RX") (pin "1") (pinfunction "A_1") (pintype "passive"))
      (node (ref "S1") (pin "3") (pinfunction "3_3") (pintype "passive"))
      (node (ref "SCREEN") (pin "1") (pinfunction "VCC_1") (pintype "passive"))
      (node (ref "SCREEN") (pin "6") (pinfunction "External_Clock_6") (pintype "passive"))
      (node (ref "TF") (pin "4") (pinfunction "VDD_4") (pintype "passive"))
      (node (ref "TX") (pin "1") (pinfunction "A_1") (pintype "passive"))
      (node (ref "U1") (pin "18") (pinfunction "AVCC_18") (pintype "passive"))
      (node (ref "U1") (pin "20") (pinfunction "AREF_20") (pintype "passive"))
      (node (ref "U1") (pin "4") (pinfunction "VCC_4") (pintype "passive"))
      (node (ref "U1") (pin "6") (pinfunction "VCC_6") (pintype "passive"))
      (node (ref "U3") (pin "4") (pinfunction "VCCIO_4") (pintype "passive"))
      (node (ref "U5") (pin "13") (pinfunction "VDD_13") (pintype "passive"))
      (node (ref "U5") (pin "8") (pinfunction "VLOGIC_8") (pintype "passive"))
    )
    (net (code "60") (name "VIN") (class "Default")
      (node (ref "C4") (pin "2") (pinfunction "2_2") (pintype "passive"))
      (node (ref "C5") (pin "2") (pinfunction "2_2") (pintype "passive"))
      (node (ref "CHAR") (pin "1") (pinfunction "A_1") (pintype "passive"))
      (node (ref "FULL") (pin "1") (pinfunction "A_1") (pintype "passive"))
      (node (ref "U2") (pin "4") (pinfunction "Vcc_4") (pintype "passive"))
      (node (ref "U2") (pin "8") (pinfunction "CE_8") (pintype "passive"))
      (node (ref "U3") (pin "20") (pinfunction "VCC_20") (pintype "passive"))
      (node (ref "USB(反口)") (pin "5") (pinfunction "5_5") (pintype "passive"))
    )
    (net (code "61") (name "unconnected-(S1-Pad1)") (class "Default")
      (node (ref "S1") (pin "1") (pinfunction "1_1") (pintype "passive"))
    )
    (net (code "62") (name "unconnected-(TF-CDN-Pad9)") (class "Default")
      (node (ref "TF") (pin "9") (pinfunction "CDN_9") (pintype "passive"))
    )
    (net (code "63") (name "unconnected-(TF-DATA1-Pad8)") (class "Default")
      (node (ref "TF") (pin "8") (pinfunction "DATA1_8") (pintype "passive"))
    )
    (net (code "64") (name "unconnected-(TF-DATA2-Pad1)") (class "Default")
      (node (ref "TF") (pin "1") (pinfunction "DATA2_1") (pintype "passive"))
    )
    (net (code "65") (name "unconnected-(U3-3V3OUT-Pad17)") (class "Default")
      (node (ref "U3") (pin "17") (pinfunction "3V3OUT_17") (pintype "passive"))
    )
    (net (code "66") (name "unconnected-(U3-CTS-Pad11)") (class "Default")
      (node (ref "U3") (pin "11") (pinfunction "CTS_11") (pintype "passive"))
    )
    (net (code "67") (name "unconnected-(U3-DCD-Pad10)") (class "Default")
      (node (ref "U3") (pin "10") (pinfunction "DCD_10") (pintype "passive"))
    )
    (net (code "68") (name "unconnected-(U3-DSR-Pad9)") (class "Default")
      (node (ref "U3") (pin "9") (pinfunction "DSR_9") (pintype "passive"))
    )
    (net (code "69") (name "unconnected-(U3-OSCI-Pad27)") (class "Default")
      (node (ref "U3") (pin "27") (pinfunction "OSCI_27") (pintype "passive"))
    )
    (net (code "70") (name "unconnected-(U3-OSCO-Pad28)") (class "Default")
      (node (ref "U3") (pin "28") (pinfunction "OSCO_28") (pintype "passive"))
    )
    (net (code "71") (name "unconnected-(U3-PWREN-Pad14)") (class "Default")
      (node (ref "U3") (pin "14") (pinfunction "PWREN_14") (pintype "passive"))
    )
    (net (code "72") (name "unconnected-(U3-RESET-Pad19)") (class "Default")
      (node (ref "U3") (pin "19") (pinfunction "RESET_19") (pintype "passive"))
    )
    (net (code "73") (name "unconnected-(U3-RI-Pad6)") (class "Default")
      (node (ref "U3") (pin "6") (pinfunction "RI_6") (pintype "passive"))
    )
    (net (code "74") (name "unconnected-(U3-RTS-Pad3)") (class "Default")
      (node (ref "U3") (pin "3") (pinfunction "RTS_3") (pintype "passive"))
    )
    (net (code "75") (name "unconnected-(U3-SLEEP-Pad12)") (class "Default")
      (node (ref "U3") (pin "12") (pinfunction "SLEEP_12") (pintype "passive"))
    )
    (net (code "76") (name "unconnected-(U3-TXDEN-Pad13)") (class "Default")
      (node (ref "U3") (pin "13") (pinfunction "TXDEN_13") (pintype "passive"))
    )
    (net (code "77") (name "unconnected-(U5-AUX_CL-Pad7)") (class "Default")
      (node (ref "U5") (pin "7") (pinfunction "AUX_CL_7") (pintype "passive"))
    )
    (net (code "78") (name "unconnected-(U5-AUX_DA-Pad6)") (class "Default")
      (node (ref "U5") (pin "6") (pinfunction "AUX_DA_6") (pintype "passive"))
    )
    (net (code "79") (name "unconnected-(U5-CLKOUT-Pad22)") (class "Default")
      (node (ref "U5") (pin "22") (pinfunction "CLKOUT_22") (pintype "passive"))
    )
    (net (code "80") (name "unconnected-(U5-INT-Pad12)") (class "Default")
      (node (ref "U5") (pin "12") (pinfunction "INT_12") (pintype "passive"))
    )
    (net (code "81") (name "unconnected-(U5-NC-Pad2)") (class "Default")
      (node (ref "U5") (pin "2") (pinfunction "NC_2") (pintype "passive"))
    )
    (net (code "82") (name "unconnected-(U5-NC-Pad3)") (class "Default")
      (node (ref "U5") (pin "3") (pinfunction "NC_3") (pintype "passive"))
    )
    (net (code "83") (name "unconnected-(U5-NC-Pad4)") (class "Default")
      (node (ref "U5") (pin "4") (pinfunction "NC_4") (pintype "passive"))
    )
    (net (code "84") (name "unconnected-(U5-NC-Pad5)") (class "Default")
      (node (ref "U5") (pin "5") (pinfunction "NC_5") (pintype "passive"))
    )
    (net (code "85") (name "unconnected-(U5-NC-Pad14)") (class "Default")
      (node (ref "U5") (pin "14") (pinfunction "NC_14") (pintype "passive"))
    )
    (net (code "86") (name "unconnected-(U5-NC-Pad15)") (class "Default")
      (node (ref "U5") (pin "15") (pinfunction "NC_15") (pintype "passive"))
    )
    (net (code "87") (name "unconnected-(U5-NC-Pad16)") (class "Default")
      (node (ref "U5") (pin "16") (pinfunction "NC_16") (pintype "passive"))
    )
    (net (code "88") (name "unconnected-(U5-NC-Pad17)") (class "Default")
      (node (ref "U5") (pin "17") (pinfunction "NC_17") (pintype "passive"))
    )
    (net (code "89") (name "unconnected-(U5-RESV-Pad19)") (class "Default")
      (node (ref "U5") (pin "19") (pinfunction "RESV_19") (pintype "passive"))
    )
    (net (code "90") (name "unconnected-(U5-RESV-Pad21)") (class "Default")
      (node (ref "U5") (pin "21") (pinfunction "RESV_21") (pintype "passive"))
    )
    (net (code "91") (name "unconnected-(USB(反口)-Pad2)") (class "Default")
      (node (ref "USB(反口)") (pin "2") (pinfunction "2_2") (pintype "passive"))
    )
    (net (code "92") (name "unconnected-(USB(反口)-Pad6)") (class "Default")
      (node (ref "USB(反口)") (pin "6") (pinfunction "6_6") (pintype "passive"))
    )
    (net (code "93") (name "unconnected-(USB(反口)-Pad7)") (class "Default")
      (node (ref "USB(反口)") (pin "7") (pinfunction "7_7") (pintype "passive"))
    )
    (net (code "94") (name "unconnected-(USB(反口)-Pad8)") (class "Default")
      (node (ref "USB(反口)") (pin "8") (pinfunction "8_8") (pintype "passive"))
    )
    (net (code "95") (name "unconnected-(USB(反口)-Pad9)") (class "Default")
      (node (ref "USB(反口)") (pin "9") (pinfunction "9_9") (pintype "passive"))
    )
    (net (code "96") (name "unconnected-(USB(反口)-Pad10)") (class "Default")
      (node (ref "USB(反口)") (pin "10") (pinfunction "10_10") (pintype "passive"))
    )
    (net (code "97") (name "unconnected-(USB(反口)-Pad11)") (class "Default")
      (node (ref "USB(反口)") (pin "11") (pinfunction "11_11") (pintype "passive"))
    )
  )
)
